# Power.net
KiCad netlist of a schematic drawn in Altium Designer
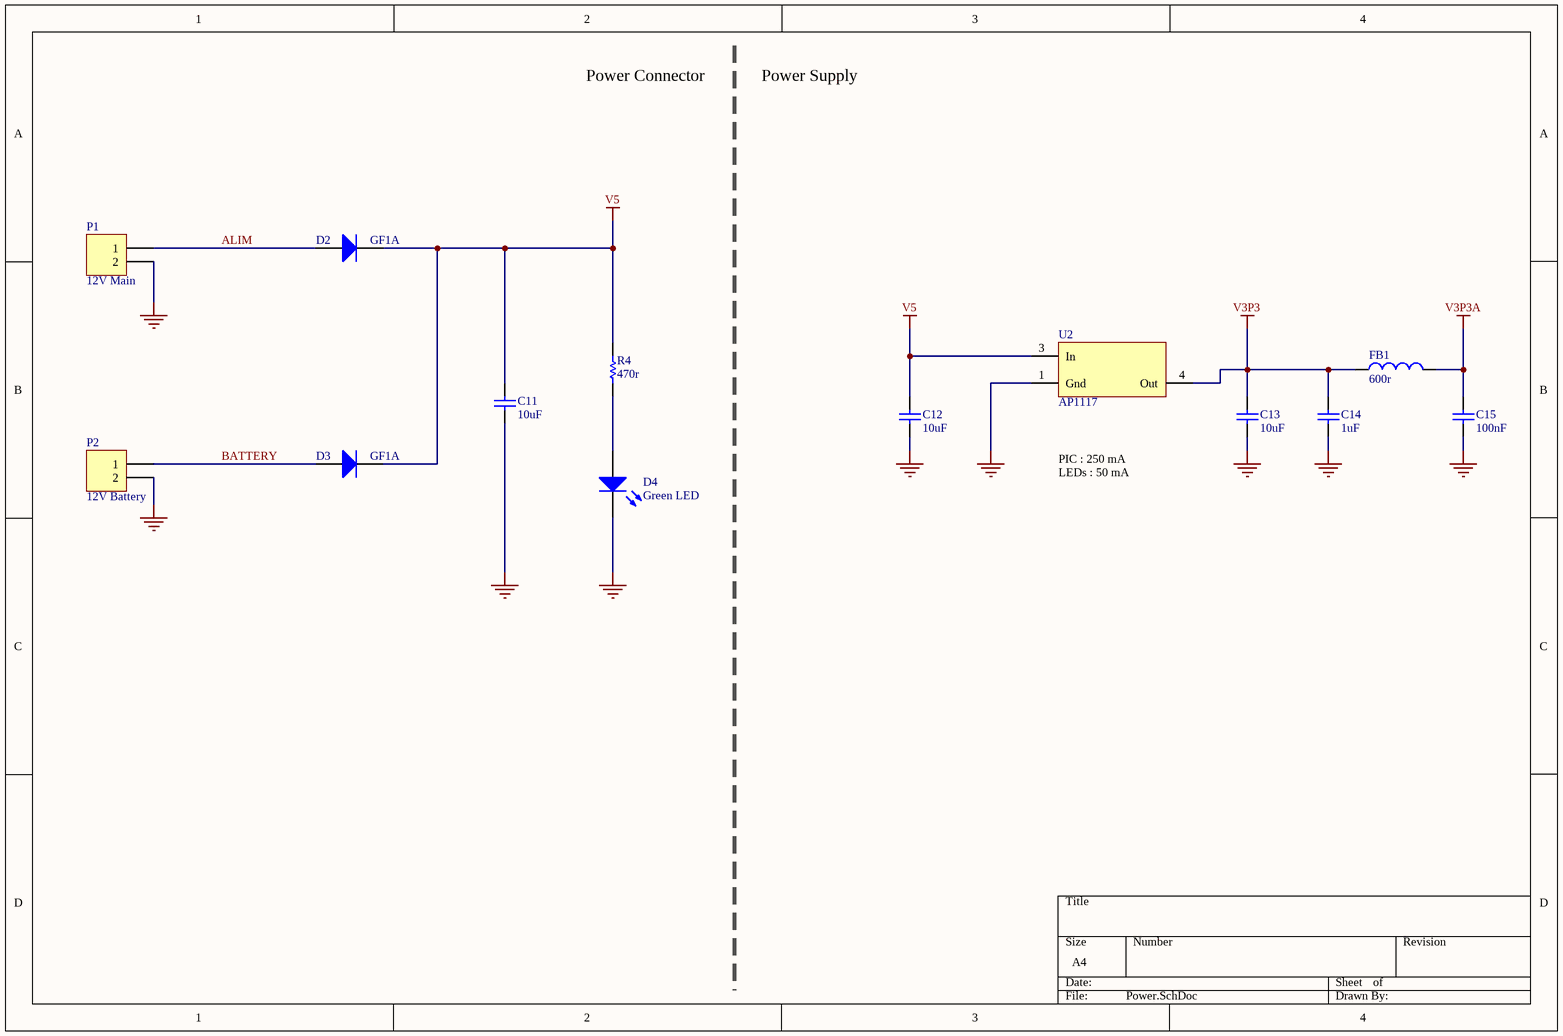
[diagram p0: Power.SchDoc]

(export (version "E")
  (design (tool "Eeschema 10.0.6"))
  (components
    (comp (ref "C11")
      (value "10uF")
      (footprint "TP2_PcbLib:CAPC2012N")
      (description "Capacitor")
      (fields (field (name "PUBLISHER") "Altium Limited"))
      (libsource (lib "Miscellaneous Devices") (part "Cap"))
    )
    (comp (ref "C12")
      (value "10uF")
      (footprint "TP2_PcbLib:CAPC2012N")
      (description "Capacitor")
      (fields (field (name "PUBLISHER") "Altium Limited"))
      (libsource (lib "Miscellaneous Devices") (part "Cap"))
    )
    (comp (ref "C13")
      (value "10uF")
      (footprint "TP2_PcbLib:CAPC2012N")
      (description "Capacitor")
      (fields (field (name "PUBLISHER") "Altium Limited"))
      (libsource (lib "Miscellaneous Devices") (part "Cap"))
    )
    (comp (ref "C14")
      (value "1uF")
      (footprint "TP2_PcbLib:CAPC1608N")
      (description "Capacitor")
      (fields (field (name "PUBLISHER") "Altium Limited"))
      (libsource (lib "Miscellaneous Devices") (part "Cap"))
    )
    (comp (ref "C15")
      (value "100nF")
      (footprint "TP2_PcbLib:CAPC1608N")
      (description "Capacitor")
      (fields (field (name "PUBLISHER") "Altium Limited"))
      (libsource (lib "Miscellaneous Devices") (part "Cap"))
    )
    (comp (ref "D2")
      (value "GF1A")
      (footprint "TP2_PcbLib:SMA/DO-214AC_21")
      (description "Default Diode")
      (fields (field (name "PUBLISHER") "Altium Limited"))
      (libsource (lib "Miscellaneous Devices") (part "Diode"))
    )
    (comp (ref "D3")
      (value "GF1A")
      (footprint "TP2_PcbLib:SMA/DO-214AC_21")
      (description "Default Diode")
      (fields (field (name "PUBLISHER") "Altium Limited"))
      (libsource (lib "Miscellaneous Devices") (part "Diode"))
    )
    (comp (ref "D4")
      (value "Green LED")
      (footprint "TP2_PcbLib:LED 0805")
      (description "Typical RED, GREEN, YELLOW, AMBER GaAs LED")
      (fields (field (name "PUBLISHER") "Altium Limited"))
      (libsource (lib "Miscellaneous Devices") (part "LED2"))
    )
    (comp (ref "FB1")
      (value "600r")
      (footprint "TP2_PcbLib:INDC1608AN")
      (description "Inductor")
      (fields (field (name "PUBLISHER") "Altium Limited"))
      (libsource (lib "Miscellaneous Devices") (part "Inductor"))
    )
    (comp (ref "P1")
      (value "12V Main")
      (footprint "TP2_PcbLib:PHOENIX_1985195")
      (description "Header, 2-Pin")
      (fields (field (name "PUBLISHER") "Altium Limited"))
      (libsource (lib "Miscellaneous Connectors") (part "Header 2"))
    )
    (comp (ref "P2")
      (value "12V Battery")
      (footprint "TP2_PcbLib:PHOENIX_1985195")
      (description "Header, 2-Pin")
      (fields (field (name "PUBLISHER") "Altium Limited"))
      (libsource (lib "Miscellaneous Connectors") (part "Header 2"))
    )
    (comp (ref "R4")
      (value "470r")
      (footprint "TP2_PcbLib:RESC1608N")
      (description "Resistor")
      (fields (field (name "PUBLISHER") "Altium Limited"))
      (libsource (lib "Miscellaneous Devices") (part "Res1"))
    )
    (comp (ref "U2")
      (value "AP1117")
      (footprint "TP2_PcbLib:TD03B_N")
      (libsource (lib "regulator") (part "AP1117"))
    )
  )
  (nets
    (net (code "1") (name "/ALIM") (class "Default")
      (node (ref "D2") (pin "1") (pinfunction "A_1") (pintype "passive"))
      (node (ref "P1") (pin "1") (pinfunction "1_1") (pintype "passive"))
    )
    (net (code "2") (name "/BATTERY") (class "Default")
      (node (ref "D3") (pin "1") (pinfunction "A_1") (pintype "passive"))
      (node (ref "P2") (pin "1") (pinfunction "1_1") (pintype "passive"))
    )
    (net (code "3") (name "GND") (class "Default")
      (node (ref "C11") (pin "1") (pinfunction "1_1") (pintype "passive"))
      (node (ref "C12") (pin "1") (pinfunction "1_1") (pintype "passive"))
      (node (ref "C13") (pin "1") (pinfunction "1_1") (pintype "passive"))
      (node (ref "C14") (pin "1") (pinfunction "1_1") (pintype "passive"))
      (node (ref "C15") (pin "1") (pinfunction "1_1") (pintype "passive"))
      (node (ref "D4") (pin "2") (pinfunction "K_2") (pintype "passive"))
      (node (ref "P1") (pin "2") (pinfunction "2_2") (pintype "passive"))
      (node (ref "P2") (pin "2") (pinfunction "2_2") (pintype "passive"))
      (node (ref "U2") (pin "1") (pinfunction "Gnd_1") (pintype "passive"))
    )
    (net (code "4") (name "Net-(D4-A)") (class "Default")
      (node (ref "D4") (pin "1") (pinfunction "A_1") (pintype "passive"))
      (node (ref "R4") (pin "1") (pinfunction "1_1") (pintype "passive"))
    )
    (net (code "5") (name "V3P3") (class "Default")
      (node (ref "C13") (pin "2") (pinfunction "2_2") (pintype "passive"))
      (node (ref "C14") (pin "2") (pinfunction "2_2") (pintype "passive"))
      (node (ref "FB1") (pin "1") (pinfunction "1_1") (pintype "passive"))
      (node (ref "U2") (pin "4") (pinfunction "Out_4") (pintype "passive"))
    )
    (net (code "6") (name "V3P3A") (class "Default")
      (node (ref "C15") (pin "2") (pinfunction "2_2") (pintype "passive"))
      (node (ref "FB1") (pin "2") (pinfunction "2_2") (pintype "passive"))
    )
    (net (code "7") (name "V5") (class "Default")
      (node (ref "C11") (pin "2") (pinfunction "2_2") (pintype "passive"))
      (node (ref "C12") (pin "2") (pinfunction "2_2") (pintype "passive"))
      (node (ref "D2") (pin "2") (pinfunction "K_2") (pintype "passive"))
      (node (ref "D3") (pin "2") (pinfunction "K_2") (pintype "passive"))
      (node (ref "R4") (pin "2") (pinfunction "2_2") (pintype "passive"))
      (node (ref "U2") (pin "3") (pinfunction "In_3") (pintype "passive"))
    )
  )
)
